# VMCustom.net
KiCad netlist of a schematic drawn in EAGLE
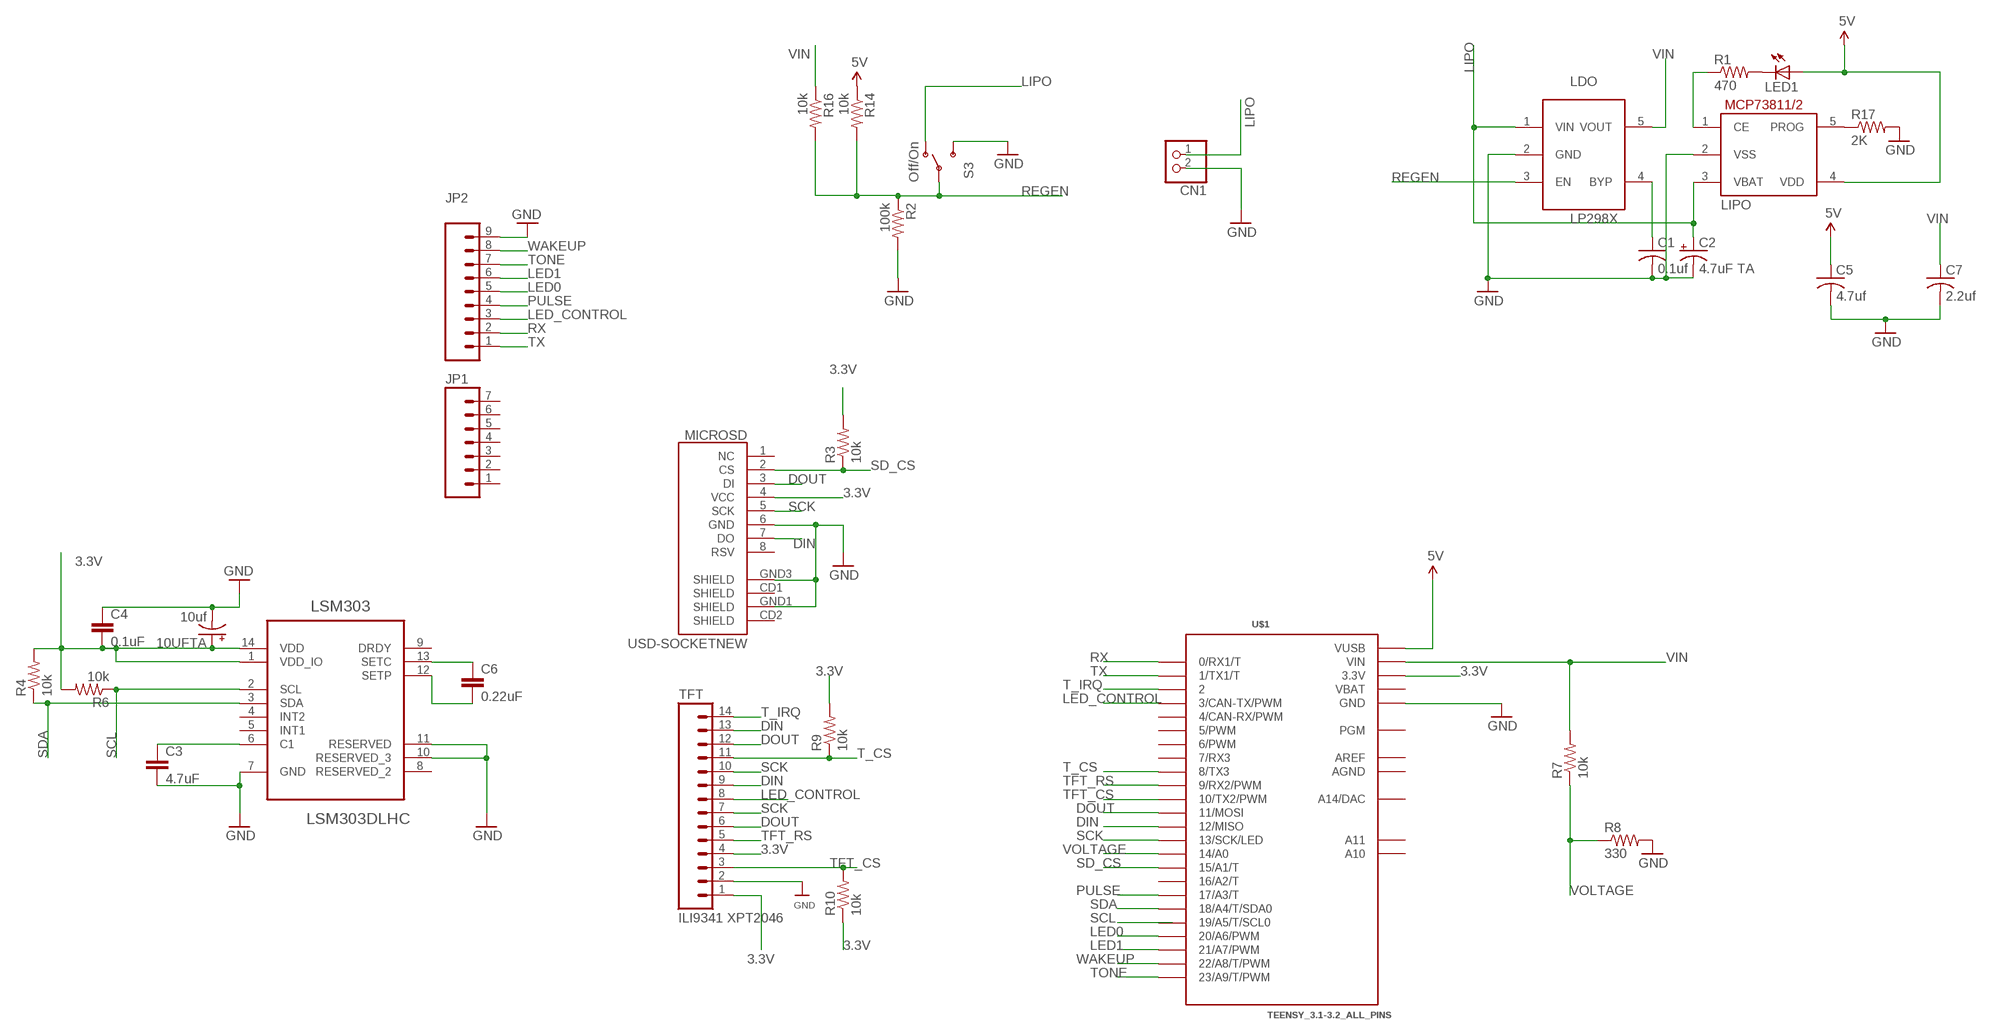
[diagram p0: schematic, sheet 1]

(export (version "E")
  (design (tool "Eeschema 10.0.6"))
  (components
    (comp (ref "10UFTA")
      (value "10uf")
      (footprint "eagle-import:EIA6032")
      (libsource (lib "eagle-import") (part "CAP_POL6032"))
    )
    (comp (ref "C1")
      (value "0.1uf")
      (footprint "eagle-import:C0805K")
      (libsource (lib "eagle-import") (part "C-USC0805K"))
    )
    (comp (ref "C2")
      (value "4.7uF TA")
      (footprint "eagle-import:EIA3216")
      (libsource (lib "eagle-import") (part "10UF-16V-10%(TANT)"))
    )
    (comp (ref "C3")
      (value "4.7uF")
      (footprint "eagle-import:0805")
      (libsource (lib "eagle-import") (part "CAP0805"))
    )
    (comp (ref "C4")
      (value "0.1uF")
      (footprint "eagle-import:0805")
      (libsource (lib "eagle-import") (part "CAP0805"))
    )
    (comp (ref "C5")
      (value "4.7uf")
      (footprint "eagle-import:C0805K")
      (libsource (lib "eagle-import") (part "C-USC0805K"))
    )
    (comp (ref "C6")
      (value "0.22uF")
      (footprint "eagle-import:0805")
      (libsource (lib "eagle-import") (part "CAP0805"))
    )
    (comp (ref "C7")
      (value "2.2uf")
      (footprint "eagle-import:C0805K")
      (libsource (lib "eagle-import") (part "C-USC0805K"))
    )
    (comp (ref "CN1")
      (value "JST_2PIN-THM")
      (footprint "eagle-import:JST-PH-2-THM")
      (libsource (lib "eagle-import") (part "JST_2PIN-THM"))
    )
    (comp (ref "JP1")
      (value "M07")
      (footprint "eagle-import:1X07")
      (libsource (lib "eagle-import") (part "M07"))
    )
    (comp (ref "JP2")
      (value "M09NO_SILK")
      (footprint "eagle-import:1X09_NO_SILK")
      (libsource (lib "eagle-import") (part "M09NO_SILK"))
    )
    (comp (ref "LDO")
      (value "LP298XS")
      (footprint "eagle-import:SOT23-5L")
      (libsource (lib "eagle-import") (part "LP298XS"))
    )
    (comp (ref "LED1")
      (value "LEDCHIPLED_0805")
      (footprint "eagle-import:CHIPLED_0805")
      (libsource (lib "eagle-import") (part "LEDCHIPLED_0805"))
    )
    (comp (ref "LIPO")
      (value "MCP73811/2")
      (footprint "eagle-import:SOT23-5L")
      (libsource (lib "eagle-import") (part "MCP73811/2"))
    )
    (comp (ref "LSM303")
      (value "LSM303DLHC")
      (footprint "eagle-import:LGA14R80P1X6")
      (libsource (lib "eagle-import") (part "LSM303DLHC"))
    )
    (comp (ref "MICROSD")
      (value "USD-SOCKETNEW")
      (footprint "eagle-import:MICRO-SD-SOCKET-PP")
      (libsource (lib "eagle-import") (part "USD-SOCKETNEW"))
    )
    (comp (ref "R1")
      (value "470")
      (footprint "eagle-import:M0805")
      (libsource (lib "eagle-import") (part "R-US_M0805"))
    )
    (comp (ref "R2")
      (value "100k")
      (footprint "eagle-import:R0805")
      (libsource (lib "eagle-import") (part "R-US_R0805"))
    )
    (comp (ref "R3")
      (value "10k")
      (footprint "eagle-import:0805")
      (libsource (lib "eagle-import") (part "RESISTOR0805-RES"))
    )
    (comp (ref "R4")
      (value "10k")
      (footprint "eagle-import:0805")
      (libsource (lib "eagle-import") (part "RESISTOR0805-RES"))
    )
    (comp (ref "R6")
      (value "10k")
      (footprint "eagle-import:0805")
      (libsource (lib "eagle-import") (part "RESISTOR0805-RES"))
    )
    (comp (ref "R7")
      (value "10k")
      (footprint "eagle-import:0805")
      (libsource (lib "eagle-import") (part "RESISTOR0805-RES"))
    )
    (comp (ref "R8")
      (value "330")
      (footprint "eagle-import:0805")
      (libsource (lib "eagle-import") (part "RESISTOR0805-RES"))
    )
    (comp (ref "R9")
      (value "10k")
      (footprint "eagle-import:0805")
      (libsource (lib "eagle-import") (part "RESISTOR0805-RES"))
    )
    (comp (ref "R10")
      (value "10k")
      (footprint "eagle-import:0805")
      (libsource (lib "eagle-import") (part "RESISTOR0805-RES"))
    )
    (comp (ref "R14")
      (value "10k")
      (footprint "eagle-import:R0805")
      (libsource (lib "eagle-import") (part "R-US_R0805"))
    )
    (comp (ref "R16")
      (value "10k")
      (footprint "eagle-import:R0805")
      (libsource (lib "eagle-import") (part "R-US_R0805"))
    )
    (comp (ref "R17")
      (value "2K")
      (footprint "eagle-import:M0805")
      (libsource (lib "eagle-import") (part "R-US_M0805"))
    )
    (comp (ref "S3")
      (value "Off/On")
      (footprint "eagle-import:SWITCH-SPST-SMD-A")
      (libsource (lib "eagle-import") (part "SWITCH-SPDT-SMD-A"))
    )
    (comp (ref "TFT")
      (value "ILI9341 XPT2046")
      (footprint "eagle-import:1X14")
      (libsource (lib "eagle-import") (part "M14"))
    )
    (comp (ref "U$1")
      (value "TEENSY_3.1-3.2_ALL_PINS")
      (footprint "eagle-import:TEENSY_3.0-3.2&LC_ALL_PINS")
      (libsource (lib "eagle-import") (part "TEENSY_3.1-3.2_ALL_PINS"))
    )
  )
  (nets
    (net (code "1") (name "/3.3V") (class "Default")
      (node (ref "10UFTA") (pin "P$1") (pinfunction "+_P$1") (pintype "passive"))
      (node (ref "C4") (pin "2") (pinfunction "2_2") (pintype "passive"))
      (node (ref "LSM303") (pin "1") (pinfunction "VDD_IO_1") (pintype "power_in"))
      (node (ref "LSM303") (pin "14") (pinfunction "VDD_14") (pintype "power_in"))
      (node (ref "MICROSD") (pin "4") (pinfunction "VCC_4") (pintype "bidirectional"))
      (node (ref "R10") (pin "1") (pinfunction "1_1") (pintype "passive"))
      (node (ref "R3") (pin "2") (pinfunction "2_2") (pintype "passive"))
      (node (ref "R4") (pin "2") (pinfunction "2_2") (pintype "passive"))
      (node (ref "R6") (pin "2") (pinfunction "2_2") (pintype "passive"))
      (node (ref "R9") (pin "2") (pinfunction "2_2") (pintype "passive"))
      (node (ref "TFT") (pin "1") (pinfunction "1_1") (pintype "passive"))
      (node (ref "TFT") (pin "4") (pinfunction "4_4") (pintype "passive"))
      (node (ref "U$1") (pin "3.3V") (pinfunction "3.3V_3.3V") (pintype "power_in"))
      (node (ref "U$1") (pin "3.3V1") (pinfunction "3.3V_3.3V1") (pintype "power_in"))
    )
    (net (code "2") (name "/AGND") (class "Default")
      (node (ref "U$1") (pin "AGND") (pinfunction "AGND_AGND") (pintype "power_in"))
    )
    (net (code "3") (name "/AREF") (class "Default")
      (node (ref "U$1") (pin "AREF") (pinfunction "AREF_AREF") (pintype "power_in"))
    )
    (net (code "4") (name "/DIN") (class "Default")
      (node (ref "MICROSD") (pin "7") (pinfunction "DO_7") (pintype "bidirectional"))
      (node (ref "TFT") (pin "13") (pinfunction "13_13") (pintype "passive"))
      (node (ref "TFT") (pin "9") (pinfunction "9_9") (pintype "passive"))
      (node (ref "U$1") (pin "12") (pinfunction "12/MISO_12") (pintype "bidirectional"))
    )
    (net (code "5") (name "/DOUT") (class "Default")
      (node (ref "MICROSD") (pin "3") (pinfunction "DI_3") (pintype "bidirectional"))
      (node (ref "TFT") (pin "12") (pinfunction "12_12") (pintype "passive"))
      (node (ref "TFT") (pin "6") (pinfunction "6_6") (pintype "passive"))
      (node (ref "U$1") (pin "11") (pinfunction "11/MOSI_11") (pintype "bidirectional"))
    )
    (net (code "6") (name "/LED0") (class "Default")
      (node (ref "JP2") (pin "5") (pinfunction "5_5") (pintype "passive"))
      (node (ref "U$1") (pin "20/A6") (pinfunction "20/A6/PWM_20/A6") (pintype "bidirectional"))
    )
    (net (code "7") (name "/LED1") (class "Default")
      (node (ref "JP2") (pin "6") (pinfunction "6_6") (pintype "passive"))
      (node (ref "U$1") (pin "21/A7") (pinfunction "21/A7/PWM_21/A7") (pintype "bidirectional"))
    )
    (net (code "8") (name "/LED_CONTROL") (class "Default")
      (node (ref "JP2") (pin "3") (pinfunction "3_3") (pintype "passive"))
      (node (ref "TFT") (pin "8") (pinfunction "8_8") (pintype "passive"))
      (node (ref "U$1") (pin "3") (pinfunction "3/CAN-TX/PWM_3") (pintype "bidirectional"))
    )
    (net (code "9") (name "/LIPO") (class "Default")
      (node (ref "C2") (pin "A") (pinfunction "+_A") (pintype "passive"))
      (node (ref "CN1") (pin "1") (pinfunction "2_1") (pintype "passive"))
      (node (ref "LDO") (pin "1") (pinfunction "VIN_1") (pintype "bidirectional"))
      (node (ref "LIPO") (pin "3") (pinfunction "VBAT_3") (pintype "bidirectional"))
      (node (ref "S3") (pin "1") (pinfunction "O_1") (pintype "passive"))
    )
    (net (code "10") (name "/PULSE") (class "Default")
      (node (ref "JP2") (pin "4") (pinfunction "4_4") (pintype "passive"))
      (node (ref "U$1") (pin "17/A3") (pinfunction "17/A3/T_17/A3") (pintype "bidirectional"))
    )
    (net (code "11") (name "/REGEN") (class "Default")
      (node (ref "LDO") (pin "3") (pinfunction "EN_3") (pintype "bidirectional"))
      (node (ref "R14") (pin "2") (pinfunction "2_2") (pintype "passive"))
      (node (ref "R16") (pin "2") (pinfunction "2_2") (pintype "passive"))
      (node (ref "R2") (pin "1") (pinfunction "1_1") (pintype "passive"))
      (node (ref "S3") (pin "2") (pinfunction "P_2") (pintype "passive"))
    )
    (net (code "12") (name "/RX") (class "Default")
      (node (ref "JP2") (pin "2") (pinfunction "2_2") (pintype "passive"))
      (node (ref "U$1") (pin "0") (pinfunction "0/RX1/T_0") (pintype "bidirectional"))
    )
    (net (code "13") (name "/SCK") (class "Default")
      (node (ref "MICROSD") (pin "5") (pinfunction "SCK_5") (pintype "bidirectional"))
      (node (ref "TFT") (pin "10") (pinfunction "10_10") (pintype "passive"))
      (node (ref "TFT") (pin "7") (pinfunction "7_7") (pintype "passive"))
      (node (ref "U$1") (pin "13") (pinfunction "13/SCK/LED_13") (pintype "bidirectional"))
    )
    (net (code "14") (name "/SCL") (class "Default")
      (node (ref "LSM303") (pin "2") (pinfunction "SCL_2") (pintype "passive"))
      (node (ref "R6") (pin "1") (pinfunction "1_1") (pintype "passive"))
      (node (ref "U$1") (pin "19/A5") (pinfunction "19/A5/T/SCL0_19/A5") (pintype "bidirectional"))
    )
    (net (code "15") (name "/SDA") (class "Default")
      (node (ref "LSM303") (pin "3") (pinfunction "SDA_3") (pintype "passive"))
      (node (ref "R4") (pin "1") (pinfunction "1_1") (pintype "passive"))
      (node (ref "U$1") (pin "18/A4") (pinfunction "18/A4/T/SDA0_18/A4") (pintype "bidirectional"))
    )
    (net (code "16") (name "/SD_CS") (class "Default")
      (node (ref "MICROSD") (pin "2") (pinfunction "CS_2") (pintype "bidirectional"))
      (node (ref "R3") (pin "1") (pinfunction "1_1") (pintype "passive"))
      (node (ref "U$1") (pin "15/A1") (pinfunction "15/A1/T_15/A1") (pintype "bidirectional"))
    )
    (net (code "17") (name "/TFT_CS") (class "Default")
      (node (ref "R10") (pin "2") (pinfunction "2_2") (pintype "passive"))
      (node (ref "TFT") (pin "3") (pinfunction "3_3") (pintype "passive"))
      (node (ref "U$1") (pin "10") (pinfunction "10/TX2/PWM_10") (pintype "bidirectional"))
    )
    (net (code "18") (name "/TFT_RS") (class "Default")
      (node (ref "TFT") (pin "5") (pinfunction "5_5") (pintype "passive"))
      (node (ref "U$1") (pin "9") (pinfunction "9/RX2/PWM_9") (pintype "bidirectional"))
    )
    (net (code "19") (name "/TONE") (class "Default")
      (node (ref "JP2") (pin "7") (pinfunction "7_7") (pintype "passive"))
      (node (ref "U$1") (pin "23/A9") (pinfunction "23/A9/T/PWM_23/A9") (pintype "bidirectional"))
    )
    (net (code "20") (name "/TX") (class "Default")
      (node (ref "JP2") (pin "1") (pinfunction "1_1") (pintype "passive"))
      (node (ref "U$1") (pin "1") (pinfunction "1/TX1/T_1") (pintype "bidirectional"))
    )
    (net (code "21") (name "/T_CS") (class "Default")
      (node (ref "R9") (pin "1") (pinfunction "1_1") (pintype "passive"))
      (node (ref "TFT") (pin "11") (pinfunction "11_11") (pintype "passive"))
      (node (ref "U$1") (pin "8") (pinfunction "8/TX3_8") (pintype "bidirectional"))
    )
    (net (code "22") (name "/T_IRQ") (class "Default")
      (node (ref "TFT") (pin "14") (pinfunction "14_14") (pintype "passive"))
      (node (ref "U$1") (pin "2") (pinfunction "2_2") (pintype "bidirectional"))
    )
    (net (code "23") (name "/VBAT") (class "Default")
      (node (ref "U$1") (pin "VBAT") (pinfunction "VBAT_VBAT") (pintype "power_in"))
    )
    (net (code "24") (name "/VIN") (class "Default")
      (node (ref "C7") (pin "1") (pinfunction "1_1") (pintype "passive"))
      (node (ref "LDO") (pin "5") (pinfunction "VOUT_5") (pintype "bidirectional"))
      (node (ref "R16") (pin "1") (pinfunction "1_1") (pintype "passive"))
      (node (ref "R7") (pin "2") (pinfunction "2_2") (pintype "passive"))
      (node (ref "U$1") (pin "VIN") (pinfunction "VIN_VIN") (pintype "power_in"))
    )
    (net (code "25") (name "/VOLTAGE") (class "Default")
      (node (ref "R7") (pin "1") (pinfunction "1_1") (pintype "passive"))
      (node (ref "R8") (pin "1") (pinfunction "1_1") (pintype "passive"))
      (node (ref "U$1") (pin "14/A0") (pinfunction "14/A0_14/A0") (pintype "bidirectional"))
    )
    (net (code "26") (name "/WAKEUP") (class "Default")
      (node (ref "JP2") (pin "8") (pinfunction "8_8") (pintype "passive"))
      (node (ref "U$1") (pin "22/A8") (pinfunction "22/A8/T/PWM_22/A8") (pintype "bidirectional"))
    )
    (net (code "27") (name "5V") (class "Default")
      (node (ref "C5") (pin "1") (pinfunction "1_1") (pintype "passive"))
      (node (ref "LED1") (pin "A") (pinfunction "A_A") (pintype "passive"))
      (node (ref "LIPO") (pin "4") (pinfunction "VDD_4") (pintype "power_in"))
      (node (ref "R14") (pin "1") (pinfunction "1_1") (pintype "passive"))
      (node (ref "U$1") (pin "VUSB") (pinfunction "VUSB_VUSB") (pintype "power_in"))
    )
    (net (code "28") (name "GND") (class "Default")
      (node (ref "10UFTA") (pin "P$2") (pinfunction "-_P$2") (pintype "passive"))
      (node (ref "C1") (pin "2") (pinfunction "2_2") (pintype "passive"))
      (node (ref "C2") (pin "C") (pinfunction "-_C") (pintype "passive"))
      (node (ref "C3") (pin "2") (pinfunction "2_2") (pintype "passive"))
      (node (ref "C4") (pin "1") (pinfunction "1_1") (pintype "passive"))
      (node (ref "C5") (pin "2") (pinfunction "2_2") (pintype "passive"))
      (node (ref "C7") (pin "2") (pinfunction "2_2") (pintype "passive"))
      (node (ref "CN1") (pin "2") (pinfunction "1_2") (pintype "passive"))
      (node (ref "JP2") (pin "9") (pinfunction "9_9") (pintype "passive"))
      (node (ref "LDO") (pin "2") (pinfunction "GND_2") (pintype "bidirectional"))
      (node (ref "LIPO") (pin "2") (pinfunction "VSS_2") (pintype "power_in"))
      (node (ref "LSM303") (pin "10") (pinfunction "RESERVED_3_10") (pintype "passive"))
      (node (ref "LSM303") (pin "11") (pinfunction "RESERVED_11") (pintype "passive"))
      (node (ref "LSM303") (pin "7") (pinfunction "GND_7") (pintype "power_in"))
      (node (ref "MICROSD") (pin "6") (pinfunction "GND_6") (pintype "bidirectional"))
      (node (ref "MICROSD") (pin "GND1") (pinfunction "SHIELD_GND1") (pintype "bidirectional"))
      (node (ref "MICROSD") (pin "GND3") (pinfunction "SHIELD_GND3") (pintype "bidirectional"))
      (node (ref "R17") (pin "2") (pinfunction "2_2") (pintype "passive"))
      (node (ref "R2") (pin "2") (pinfunction "2_2") (pintype "passive"))
      (node (ref "R8") (pin "2") (pinfunction "2_2") (pintype "passive"))
      (node (ref "S3") (pin "3") (pinfunction "S_3") (pintype "passive"))
      (node (ref "TFT") (pin "2") (pinfunction "2_2") (pintype "passive"))
      (node (ref "U$1") (pin "GND") (pinfunction "GND_GND") (pintype "power_in"))
      (node (ref "U$1") (pin "GND1") (pinfunction "GND_GND1") (pintype "power_in"))
    )
    (net (code "29") (name "Net-(LDO-BYP)") (class "Default")
      (node (ref "C1") (pin "1") (pinfunction "1_1") (pintype "passive"))
      (node (ref "LDO") (pin "4") (pinfunction "BYP_4") (pintype "bidirectional"))
    )
    (net (code "30") (name "Net-(LED1-PadC)") (class "Default")
      (node (ref "LED1") (pin "C") (pinfunction "C_C") (pintype "passive"))
      (node (ref "R1") (pin "2") (pinfunction "2_2") (pintype "passive"))
    )
    (net (code "31") (name "Net-(LIPO-CE)") (class "Default")
      (node (ref "LIPO") (pin "1") (pinfunction "CE_1") (pintype "input"))
      (node (ref "R1") (pin "1") (pinfunction "1_1") (pintype "passive"))
    )
    (net (code "32") (name "Net-(LIPO-PROG)") (class "Default")
      (node (ref "LIPO") (pin "5") (pinfunction "PROG_5") (pintype "input"))
      (node (ref "R17") (pin "1") (pinfunction "1_1") (pintype "passive"))
    )
    (net (code "33") (name "Net-(LSM303-C1)") (class "Default")
      (node (ref "C3") (pin "1") (pinfunction "1_1") (pintype "passive"))
      (node (ref "LSM303") (pin "6") (pinfunction "C1_6") (pintype "passive"))
    )
    (net (code "34") (name "Net-(LSM303-SETC)") (class "Default")
      (node (ref "C6") (pin "1") (pinfunction "1_1") (pintype "passive"))
      (node (ref "LSM303") (pin "13") (pinfunction "SETC_13") (pintype "passive"))
    )
    (net (code "35") (name "Net-(LSM303-SETP)") (class "Default")
      (node (ref "C6") (pin "2") (pinfunction "2_2") (pintype "passive"))
      (node (ref "LSM303") (pin "12") (pinfunction "SETP_12") (pintype "passive"))
    )
    (net (code "36") (name "unconnected-(JP1-Pad1)") (class "Default")
      (node (ref "JP1") (pin "1") (pinfunction "1_1") (pintype "passive"))
    )
    (net (code "37") (name "unconnected-(JP1-Pad2)") (class "Default")
      (node (ref "JP1") (pin "2") (pinfunction "2_2") (pintype "passive"))
    )
    (net (code "38") (name "unconnected-(JP1-Pad3)") (class "Default")
      (node (ref "JP1") (pin "3") (pinfunction "3_3") (pintype "passive"))
    )
    (net (code "39") (name "unconnected-(JP1-Pad4)") (class "Default")
      (node (ref "JP1") (pin "4") (pinfunction "4_4") (pintype "passive"))
    )
    (net (code "40") (name "unconnected-(JP1-Pad5)") (class "Default")
      (node (ref "JP1") (pin "5") (pinfunction "5_5") (pintype "passive"))
    )
    (net (code "41") (name "unconnected-(JP1-Pad6)") (class "Default")
      (node (ref "JP1") (pin "6") (pinfunction "6_6") (pintype "passive"))
    )
    (net (code "42") (name "unconnected-(JP1-Pad7)") (class "Default")
      (node (ref "JP1") (pin "7") (pinfunction "7_7") (pintype "passive"))
    )
    (net (code "43") (name "unconnected-(LSM303-DRDY-Pad9)") (class "Default")
      (node (ref "LSM303") (pin "9") (pinfunction "DRDY_9") (pintype "passive"))
    )
    (net (code "44") (name "unconnected-(LSM303-INT1-Pad5)") (class "Default")
      (node (ref "LSM303") (pin "5") (pinfunction "INT1_5") (pintype "passive"))
    )
    (net (code "45") (name "unconnected-(LSM303-INT2-Pad4)") (class "Default")
      (node (ref "LSM303") (pin "4") (pinfunction "INT2_4") (pintype "passive"))
    )
    (net (code "46") (name "unconnected-(LSM303-RESERVED_2-Pad8)") (class "Default")
      (node (ref "LSM303") (pin "8") (pinfunction "RESERVED_2_8") (pintype "passive"))
    )
    (net (code "47") (name "unconnected-(MICROSD-NC-Pad1)") (class "Default")
      (node (ref "MICROSD") (pin "1") (pinfunction "NC_1") (pintype "bidirectional"))
    )
    (net (code "48") (name "unconnected-(MICROSD-RSV-Pad8)") (class "Default")
      (node (ref "MICROSD") (pin "8") (pinfunction "RSV_8") (pintype "bidirectional"))
    )
    (net (code "49") (name "unconnected-(MICROSD-SHIELD-PadCD1)") (class "Default")
      (node (ref "MICROSD") (pin "CD1") (pinfunction "SHIELD_CD1") (pintype "bidirectional"))
    )
    (net (code "50") (name "unconnected-(MICROSD-SHIELD-PadCD2)") (class "Default")
      (node (ref "MICROSD") (pin "CD2") (pinfunction "SHIELD_CD2") (pintype "bidirectional"))
    )
    (net (code "51") (name "unconnected-(U$1-4{slash}CAN-RX{slash}PWM-Pad4)") (class "Default")
      (node (ref "U$1") (pin "4") (pinfunction "4/CAN-RX/PWM_4") (pintype "bidirectional"))
    )
    (net (code "52") (name "unconnected-(U$1-5{slash}PWM-Pad5)") (class "Default")
      (node (ref "U$1") (pin "5") (pinfunction "5/PWM_5") (pintype "bidirectional"))
    )
    (net (code "53") (name "unconnected-(U$1-6{slash}PWM-Pad6)") (class "Default")
      (node (ref "U$1") (pin "6") (pinfunction "6/PWM_6") (pintype "bidirectional"))
    )
    (net (code "54") (name "unconnected-(U$1-7{slash}RX3-Pad7)") (class "Default")
      (node (ref "U$1") (pin "7") (pinfunction "7/RX3_7") (pintype "bidirectional"))
    )
    (net (code "55") (name "unconnected-(U$1-16{slash}A2{slash}T-Pad16{slash}A2)") (class "Default")
      (node (ref "U$1") (pin "16/A2") (pinfunction "16/A2/T_16/A2") (pintype "bidirectional"))
    )
    (net (code "56") (name "unconnected-(U$1-A14{slash}DAC-PadRESET{slash}DAC)") (class "Default")
      (node (ref "U$1") (pin "RESET/DAC") (pinfunction "A14/DAC_RESET/DAC") (pintype "bidirectional"))
    )
    (net (code "57") (name "unconnected-(U$1-PadA10)") (class "Default")
      (node (ref "U$1") (pin "A10") (pinfunction "A10_A10") (pintype "bidirectional"))
    )
    (net (code "58") (name "unconnected-(U$1-PadA11)") (class "Default")
      (node (ref "U$1") (pin "A11") (pinfunction "A11_A11") (pintype "bidirectional"))
    )
    (net (code "59") (name "unconnected-(U$1-PadPGM)") (class "Default")
      (node (ref "U$1") (pin "PGM") (pinfunction "PGM_PGM") (pintype "bidirectional"))
    )
  )
)
